# untitled.net
KiCad netlist of a schematic drawn in EAGLE
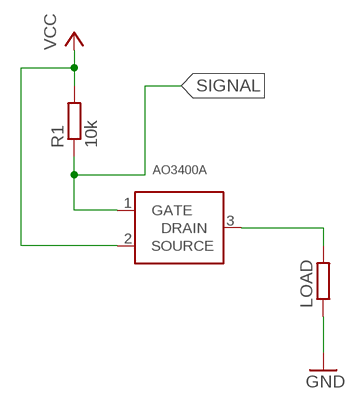
[diagram p0: schematic, sheet 1]

(export (version "E")
  (design (tool "Eeschema 10.0.6"))
  (components
    (comp (ref "AO3401_P-MOSFET")
      (value "AO3401_P-MOSFET")
      (footprint "eagle-import:SOT-23")
      (libsource (lib "eagle-import") (part "AO3400A"))
    )
    (comp (ref "LOAD")
      (value "R-EU_0204/2V")
      (footprint "eagle-import:0204V")
      (libsource (lib "eagle-import") (part "R-EU_0204/2V"))
    )
    (comp (ref "R1")
      (value "10k")
      (footprint "eagle-import:0204V")
      (libsource (lib "eagle-import") (part "R-EU_0204/2V"))
    )
  )
  (nets
    (net (code "1") (name "GND") (class "Default")
      (node (ref "LOAD") (pin "1") (pinfunction "1_1") (pintype "passive"))
    )
    (net (code "2") (name "Net-(AO3401_P-MOSFET-DRAIN)") (class "Default")
      (node (ref "AO3401_P-MOSFET") (pin "3") (pinfunction "DRAIN_3") (pintype "bidirectional"))
      (node (ref "LOAD") (pin "2") (pinfunction "2_2") (pintype "passive"))
    )
    (net (code "3") (name "SIGNAL") (class "Default")
      (node (ref "AO3401_P-MOSFET") (pin "1") (pinfunction "GATE_1") (pintype "bidirectional"))
      (node (ref "R1") (pin "1") (pinfunction "1_1") (pintype "passive"))
    )
    (net (code "4") (name "VCC") (class "Default")
      (node (ref "AO3401_P-MOSFET") (pin "2") (pinfunction "SOURCE_2") (pintype "bidirectional"))
      (node (ref "R1") (pin "2") (pinfunction "2_2") (pintype "passive"))
    )
  )
)
